# trafficLight.net
KiCad netlist of a schematic drawn in EAGLE
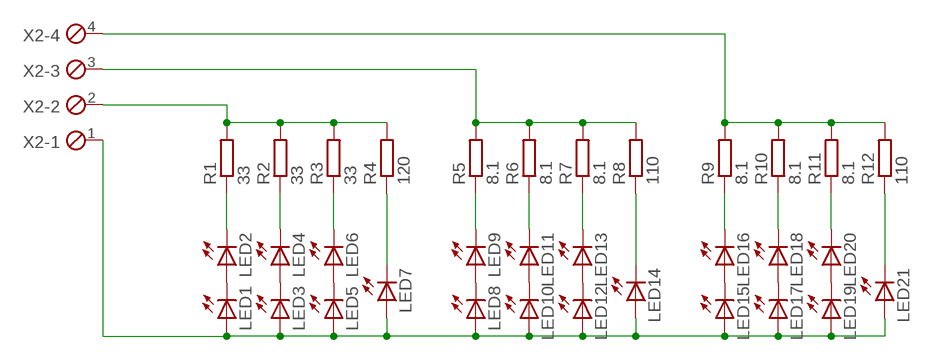
[diagram p0: schematic, sheet 1]

(export (version "E")
  (design (tool "Eeschema 10.0.6"))
  (components
    (comp (ref "LED1")
      (value "LED")
      (footprint "eagle-import:SMARTLED-TTW")
      (libsource (lib "eagle-import") (part "LED"))
    )
    (comp (ref "LED2")
      (value "LED")
      (footprint "eagle-import:SMARTLED-TTW")
      (libsource (lib "eagle-import") (part "LED"))
    )
    (comp (ref "LED3")
      (value "LED")
      (footprint "eagle-import:SMARTLED-TTW")
      (libsource (lib "eagle-import") (part "LED"))
    )
    (comp (ref "LED4")
      (value "LED")
      (footprint "eagle-import:SMARTLED-TTW")
      (libsource (lib "eagle-import") (part "LED"))
    )
    (comp (ref "LED5")
      (value "LED")
      (footprint "eagle-import:SMARTLED-TTW")
      (libsource (lib "eagle-import") (part "LED"))
    )
    (comp (ref "LED6")
      (value "LED")
      (footprint "eagle-import:SMARTLED-TTW")
      (libsource (lib "eagle-import") (part "LED"))
    )
    (comp (ref "LED7")
      (value "LED")
      (footprint "eagle-import:SMARTLED-TTW")
      (libsource (lib "eagle-import") (part "LED"))
    )
    (comp (ref "LED8")
      (value "LED")
      (footprint "eagle-import:SMARTLED-TTW")
      (libsource (lib "eagle-import") (part "LED"))
    )
    (comp (ref "LED9")
      (value "LED")
      (footprint "eagle-import:SMARTLED-TTW")
      (libsource (lib "eagle-import") (part "LED"))
    )
    (comp (ref "LED10")
      (value "LED")
      (footprint "eagle-import:SMARTLED-TTW")
      (libsource (lib "eagle-import") (part "LED"))
    )
    (comp (ref "LED11")
      (value "LED")
      (footprint "eagle-import:SMARTLED-TTW")
      (libsource (lib "eagle-import") (part "LED"))
    )
    (comp (ref "LED12")
      (value "LED")
      (footprint "eagle-import:SMARTLED-TTW")
      (libsource (lib "eagle-import") (part "LED"))
    )
    (comp (ref "LED13")
      (value "LED")
      (footprint "eagle-import:SMARTLED-TTW")
      (libsource (lib "eagle-import") (part "LED"))
    )
    (comp (ref "LED14")
      (value "LED")
      (footprint "eagle-import:SMARTLED-TTW")
      (libsource (lib "eagle-import") (part "LED"))
    )
    (comp (ref "LED15")
      (value "LED")
      (footprint "eagle-import:SMARTLED-TTW")
      (libsource (lib "eagle-import") (part "LED"))
    )
    (comp (ref "LED16")
      (value "LED")
      (footprint "eagle-import:SMARTLED-TTW")
      (libsource (lib "eagle-import") (part "LED"))
    )
    (comp (ref "LED17")
      (value "LED")
      (footprint "eagle-import:SMARTLED-TTW")
      (libsource (lib "eagle-import") (part "LED"))
    )
    (comp (ref "LED18")
      (value "LED")
      (footprint "eagle-import:SMARTLED-TTW")
      (libsource (lib "eagle-import") (part "LED"))
    )
    (comp (ref "LED19")
      (value "LED")
      (footprint "eagle-import:SMARTLED-TTW")
      (libsource (lib "eagle-import") (part "LED"))
    )
    (comp (ref "LED20")
      (value "LED")
      (footprint "eagle-import:SMARTLED-TTW")
      (libsource (lib "eagle-import") (part "LED"))
    )
    (comp (ref "LED21")
      (value "LED")
      (footprint "eagle-import:SMARTLED-TTW")
      (libsource (lib "eagle-import") (part "LED"))
    )
    (comp (ref "R1")
      (value "33")
      (footprint "eagle-import:0204_7")
      (libsource (lib "eagle-import") (part "R-EU_0204/7"))
    )
    (comp (ref "R2")
      (value "33")
      (footprint "eagle-import:0204_7")
      (libsource (lib "eagle-import") (part "R-EU_0204/7"))
    )
    (comp (ref "R3")
      (value "33")
      (footprint "eagle-import:0204_7")
      (libsource (lib "eagle-import") (part "R-EU_0204/7"))
    )
    (comp (ref "R4")
      (value "120")
      (footprint "eagle-import:0204_7")
      (libsource (lib "eagle-import") (part "R-EU_0204/7"))
    )
    (comp (ref "R5")
      (value "8.1")
      (footprint "eagle-import:0204_7")
      (libsource (lib "eagle-import") (part "R-EU_0204/7"))
    )
    (comp (ref "R6")
      (value "8.1")
      (footprint "eagle-import:0204_7")
      (libsource (lib "eagle-import") (part "R-EU_0204/7"))
    )
    (comp (ref "R7")
      (value "8.1")
      (footprint "eagle-import:0204_7")
      (libsource (lib "eagle-import") (part "R-EU_0204/7"))
    )
    (comp (ref "R8")
      (value "110")
      (footprint "eagle-import:0204_7")
      (libsource (lib "eagle-import") (part "R-EU_0204/7"))
    )
    (comp (ref "R9")
      (value "8.1")
      (footprint "eagle-import:0204_7")
      (libsource (lib "eagle-import") (part "R-EU_0204/7"))
    )
    (comp (ref "R10")
      (value "8.1")
      (footprint "eagle-import:0204_7")
      (libsource (lib "eagle-import") (part "R-EU_0204/7"))
    )
    (comp (ref "R11")
      (value "8.1")
      (footprint "eagle-import:0204_7")
      (libsource (lib "eagle-import") (part "R-EU_0204/7"))
    )
    (comp (ref "R12")
      (value "110")
      (footprint "eagle-import:0204_7")
      (libsource (lib "eagle-import") (part "R-EU_0204/7"))
    )
    (comp (ref "X2")
      (value "MPT4")
      (footprint "eagle-import:4POL254")
      (libsource (lib "eagle-import") (part "MPT4"))
    )
  )
  (nets
    (net (code "1") (name "Net-(LED1-A)") (class "Default")
      (node (ref "LED1") (pin "A@1") (pinfunction "A_A@1") (pintype "passive"))
      (node (ref "LED10") (pin "A@1") (pinfunction "A_A@1") (pintype "passive"))
      (node (ref "LED12") (pin "A@1") (pinfunction "A_A@1") (pintype "passive"))
      (node (ref "LED14") (pin "A@1") (pinfunction "A_A@1") (pintype "passive"))
      (node (ref "LED15") (pin "A@1") (pinfunction "A_A@1") (pintype "passive"))
      (node (ref "LED17") (pin "A@1") (pinfunction "A_A@1") (pintype "passive"))
      (node (ref "LED19") (pin "A@1") (pinfunction "A_A@1") (pintype "passive"))
      (node (ref "LED21") (pin "A@1") (pinfunction "A_A@1") (pintype "passive"))
      (node (ref "LED3") (pin "A@1") (pinfunction "A_A@1") (pintype "passive"))
      (node (ref "LED5") (pin "A@1") (pinfunction "A_A@1") (pintype "passive"))
      (node (ref "LED7") (pin "A@1") (pinfunction "A_A@1") (pintype "passive"))
      (node (ref "LED8") (pin "A@1") (pinfunction "A_A@1") (pintype "passive"))
      (node (ref "X2") (pin "1") (pinfunction "1_1") (pintype "passive"))
    )
    (net (code "2") (name "Net-(LED1-C)") (class "Default")
      (node (ref "LED1") (pin "C@1") (pinfunction "C_C@1") (pintype "passive"))
      (node (ref "LED2") (pin "A@1") (pinfunction "A_A@1") (pintype "passive"))
    )
    (net (code "3") (name "Net-(LED2-C)") (class "Default")
      (node (ref "LED2") (pin "C@1") (pinfunction "C_C@1") (pintype "passive"))
      (node (ref "R1") (pin "1") (pinfunction "1_1") (pintype "passive"))
    )
    (net (code "4") (name "Net-(LED3-C)") (class "Default")
      (node (ref "LED3") (pin "C@1") (pinfunction "C_C@1") (pintype "passive"))
      (node (ref "LED4") (pin "A@1") (pinfunction "A_A@1") (pintype "passive"))
    )
    (net (code "5") (name "Net-(LED4-C)") (class "Default")
      (node (ref "LED4") (pin "C@1") (pinfunction "C_C@1") (pintype "passive"))
      (node (ref "R2") (pin "1") (pinfunction "1_1") (pintype "passive"))
    )
    (net (code "6") (name "Net-(LED5-C)") (class "Default")
      (node (ref "LED5") (pin "C@1") (pinfunction "C_C@1") (pintype "passive"))
      (node (ref "LED6") (pin "A@1") (pinfunction "A_A@1") (pintype "passive"))
    )
    (net (code "7") (name "Net-(LED6-C)") (class "Default")
      (node (ref "LED6") (pin "C@1") (pinfunction "C_C@1") (pintype "passive"))
      (node (ref "R3") (pin "1") (pinfunction "1_1") (pintype "passive"))
    )
    (net (code "8") (name "Net-(LED7-C)") (class "Default")
      (node (ref "LED7") (pin "C@1") (pinfunction "C_C@1") (pintype "passive"))
      (node (ref "R4") (pin "1") (pinfunction "1_1") (pintype "passive"))
    )
    (net (code "9") (name "Net-(LED8-C)") (class "Default")
      (node (ref "LED8") (pin "C@1") (pinfunction "C_C@1") (pintype "passive"))
      (node (ref "LED9") (pin "A@1") (pinfunction "A_A@1") (pintype "passive"))
    )
    (net (code "10") (name "Net-(LED9-C)") (class "Default")
      (node (ref "LED9") (pin "C@1") (pinfunction "C_C@1") (pintype "passive"))
      (node (ref "R5") (pin "1") (pinfunction "1_1") (pintype "passive"))
    )
    (net (code "11") (name "Net-(LED10-C)") (class "Default")
      (node (ref "LED10") (pin "C@1") (pinfunction "C_C@1") (pintype "passive"))
      (node (ref "LED11") (pin "A@1") (pinfunction "A_A@1") (pintype "passive"))
    )
    (net (code "12") (name "Net-(LED11-C)") (class "Default")
      (node (ref "LED11") (pin "C@1") (pinfunction "C_C@1") (pintype "passive"))
      (node (ref "R6") (pin "1") (pinfunction "1_1") (pintype "passive"))
    )
    (net (code "13") (name "Net-(LED12-C)") (class "Default")
      (node (ref "LED12") (pin "C@1") (pinfunction "C_C@1") (pintype "passive"))
      (node (ref "LED13") (pin "A@1") (pinfunction "A_A@1") (pintype "passive"))
    )
    (net (code "14") (name "Net-(LED13-C)") (class "Default")
      (node (ref "LED13") (pin "C@1") (pinfunction "C_C@1") (pintype "passive"))
      (node (ref "R7") (pin "1") (pinfunction "1_1") (pintype "passive"))
    )
    (net (code "15") (name "Net-(LED14-C)") (class "Default")
      (node (ref "LED14") (pin "C@1") (pinfunction "C_C@1") (pintype "passive"))
      (node (ref "R8") (pin "1") (pinfunction "1_1") (pintype "passive"))
    )
    (net (code "16") (name "Net-(LED15-C)") (class "Default")
      (node (ref "LED15") (pin "C@1") (pinfunction "C_C@1") (pintype "passive"))
      (node (ref "LED16") (pin "A@1") (pinfunction "A_A@1") (pintype "passive"))
    )
    (net (code "17") (name "Net-(LED16-C)") (class "Default")
      (node (ref "LED16") (pin "C@1") (pinfunction "C_C@1") (pintype "passive"))
      (node (ref "R9") (pin "1") (pinfunction "1_1") (pintype "passive"))
    )
    (net (code "18") (name "Net-(LED17-C)") (class "Default")
      (node (ref "LED17") (pin "C@1") (pinfunction "C_C@1") (pintype "passive"))
      (node (ref "LED18") (pin "A@1") (pinfunction "A_A@1") (pintype "passive"))
    )
    (net (code "19") (name "Net-(LED18-C)") (class "Default")
      (node (ref "LED18") (pin "C@1") (pinfunction "C_C@1") (pintype "passive"))
      (node (ref "R10") (pin "1") (pinfunction "1_1") (pintype "passive"))
    )
    (net (code "20") (name "Net-(LED19-C)") (class "Default")
      (node (ref "LED19") (pin "C@1") (pinfunction "C_C@1") (pintype "passive"))
      (node (ref "LED20") (pin "A@1") (pinfunction "A_A@1") (pintype "passive"))
    )
    (net (code "21") (name "Net-(LED20-C)") (class "Default")
      (node (ref "LED20") (pin "C@1") (pinfunction "C_C@1") (pintype "passive"))
      (node (ref "R11") (pin "1") (pinfunction "1_1") (pintype "passive"))
    )
    (net (code "22") (name "Net-(LED21-C)") (class "Default")
      (node (ref "LED21") (pin "C@1") (pinfunction "C_C@1") (pintype "passive"))
      (node (ref "R12") (pin "1") (pinfunction "1_1") (pintype "passive"))
    )
    (net (code "23") (name "Net-(X2B-1)") (class "Default")
      (node (ref "R1") (pin "2") (pinfunction "2_2") (pintype "passive"))
      (node (ref "R2") (pin "2") (pinfunction "2_2") (pintype "passive"))
      (node (ref "R3") (pin "2") (pinfunction "2_2") (pintype "passive"))
      (node (ref "R4") (pin "2") (pinfunction "2_2") (pintype "passive"))
      (node (ref "X2") (pin "2") (pinfunction "1_2") (pintype "passive"))
    )
    (net (code "24") (name "Net-(X2C-1)") (class "Default")
      (node (ref "R5") (pin "2") (pinfunction "2_2") (pintype "passive"))
      (node (ref "R6") (pin "2") (pinfunction "2_2") (pintype "passive"))
      (node (ref "R7") (pin "2") (pinfunction "2_2") (pintype "passive"))
      (node (ref "R8") (pin "2") (pinfunction "2_2") (pintype "passive"))
      (node (ref "X2") (pin "3") (pinfunction "1_3") (pintype "passive"))
    )
    (net (code "25") (name "Net-(X2D-1)") (class "Default")
      (node (ref "R10") (pin "2") (pinfunction "2_2") (pintype "passive"))
      (node (ref "R11") (pin "2") (pinfunction "2_2") (pintype "passive"))
      (node (ref "R12") (pin "2") (pinfunction "2_2") (pintype "passive"))
      (node (ref "R9") (pin "2") (pinfunction "2_2") (pintype "passive"))
      (node (ref "X2") (pin "4") (pinfunction "1_4") (pintype "passive"))
    )
  )
)
